# Switch.net
KiCad netlist of a schematic drawn in Altium Designer
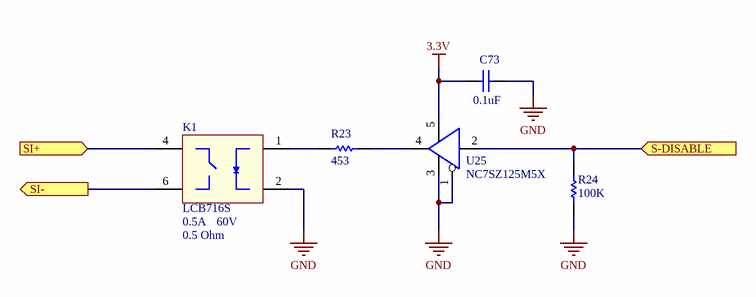
[diagram p0: Switch.SchDoc]

(export (version "E")
  (design (tool "Eeschema 10.0.6"))
  (components
    (comp (ref "C73")
      (value "0.1uF")
      (footprint "CAP-0603")
      (description "CAP CER 0.1uF 50V X7R 0603")
      (fields (field (name "PARTNUMBER") "C0603C104K5RACAUTO") (field (name "MANUFACTURER") "Kemet"))
      (libsource (lib "Kemet") (part "C0603C104K5RACAUTO"))
    )
    (comp (ref "K1")
      (value "LCB716S")
      (footprint "SMD6")
      (description "SSR RELAY SPST-NC 500MA 0-60V")
      (fields
        (field (name "MANUFACTURER") "Ixys")
        (field (name "RON") "0.5 Ohm")
        (field (name "CURRENT") "0.5A")
        (field (name "VOLTAGE") "60V")
        (field (name "PARTNUMBER") "LCB716S")
      )
      (libsource (lib "Ixys") (part "LCB716S"))
    )
    (comp (ref "R23")
      (value "453")
      (footprint "RES-0603")
      (description "RES SMD 453 OHM 1% 1/10W 0603")
      (fields (field (name "TOLERANCE") "1%") (field (name "MANUFACTURER") "Yageo"))
      (libsource (lib "Yageo") (part "RC0603FR-07453RL"))
    )
    (comp (ref "R24")
      (value "100K")
      (footprint "RES-0603")
      (description "RES SMD 100K OHM 1% 1/10W 0603")
      (fields (field (name "TOLERANCE") "1%") (field (name "MANUFACTURER") "Yageo"))
      (libsource (lib "Yageo") (part "RC0603FR-07100KL"))
    )
    (comp (ref "U25")
      (value "NC7SZ125M5X")
      (footprint "SOT23-5")
      (description "IC BUFF TRI-ST UHS N-INV SOT23-5")
      (fields
        (field (name "MANUFACTURER") "Fairchild Semiconductor")
        (field (name "PARTNUMBER") "NC7SZ125M5X")
      )
      (libsource (lib "Fairchild") (part "NC7SZ125M5X"))
    )
  )
  (nets
    (net (code "1") (name "/S-DISABLE") (class "Default")
      (node (ref "R24") (pin "2") (pinfunction "2_2") (pintype "passive"))
      (node (ref "U25") (pin "2") (pinfunction "A_2") (pintype "passive"))
    )
    (net (code "2") (name "/SI+") (class "Default")
      (node (ref "K1") (pin "4") (pinfunction "4_4") (pintype "passive"))
    )
    (net (code "3") (name "/SI-") (class "Default")
      (node (ref "K1") (pin "6") (pinfunction "6_6") (pintype "passive"))
    )
    (net (code "4") (name "3.3V") (class "Default")
      (node (ref "C73") (pin "1") (pinfunction "1_1") (pintype "passive"))
      (node (ref "U25") (pin "5") (pinfunction "VCC_5") (pintype "passive"))
    )
    (net (code "5") (name "GND") (class "Default")
      (node (ref "C73") (pin "2") (pinfunction "2_2") (pintype "passive"))
      (node (ref "K1") (pin "2") (pinfunction "2_2") (pintype "passive"))
      (node (ref "R24") (pin "1") (pinfunction "1_1") (pintype "passive"))
      (node (ref "U25") (pin "1") (pinfunction "OE_1") (pintype "passive"))
      (node (ref "U25") (pin "3") (pinfunction "GND_3") (pintype "passive"))
    )
    (net (code "6") (name "Net-(K1-Pad1)") (class "Default")
      (node (ref "K1") (pin "1") (pinfunction "1_1") (pintype "passive"))
      (node (ref "R23") (pin "1") (pinfunction "1_1") (pintype "passive"))
    )
    (net (code "7") (name "Net-(U25-Y)") (class "Default")
      (node (ref "R23") (pin "2") (pinfunction "2_2") (pintype "passive"))
      (node (ref "U25") (pin "4") (pinfunction "Y_4") (pintype "passive"))
    )
  )
)
